# schematic_smd.net
KiCad netlist of a schematic drawn in EAGLE
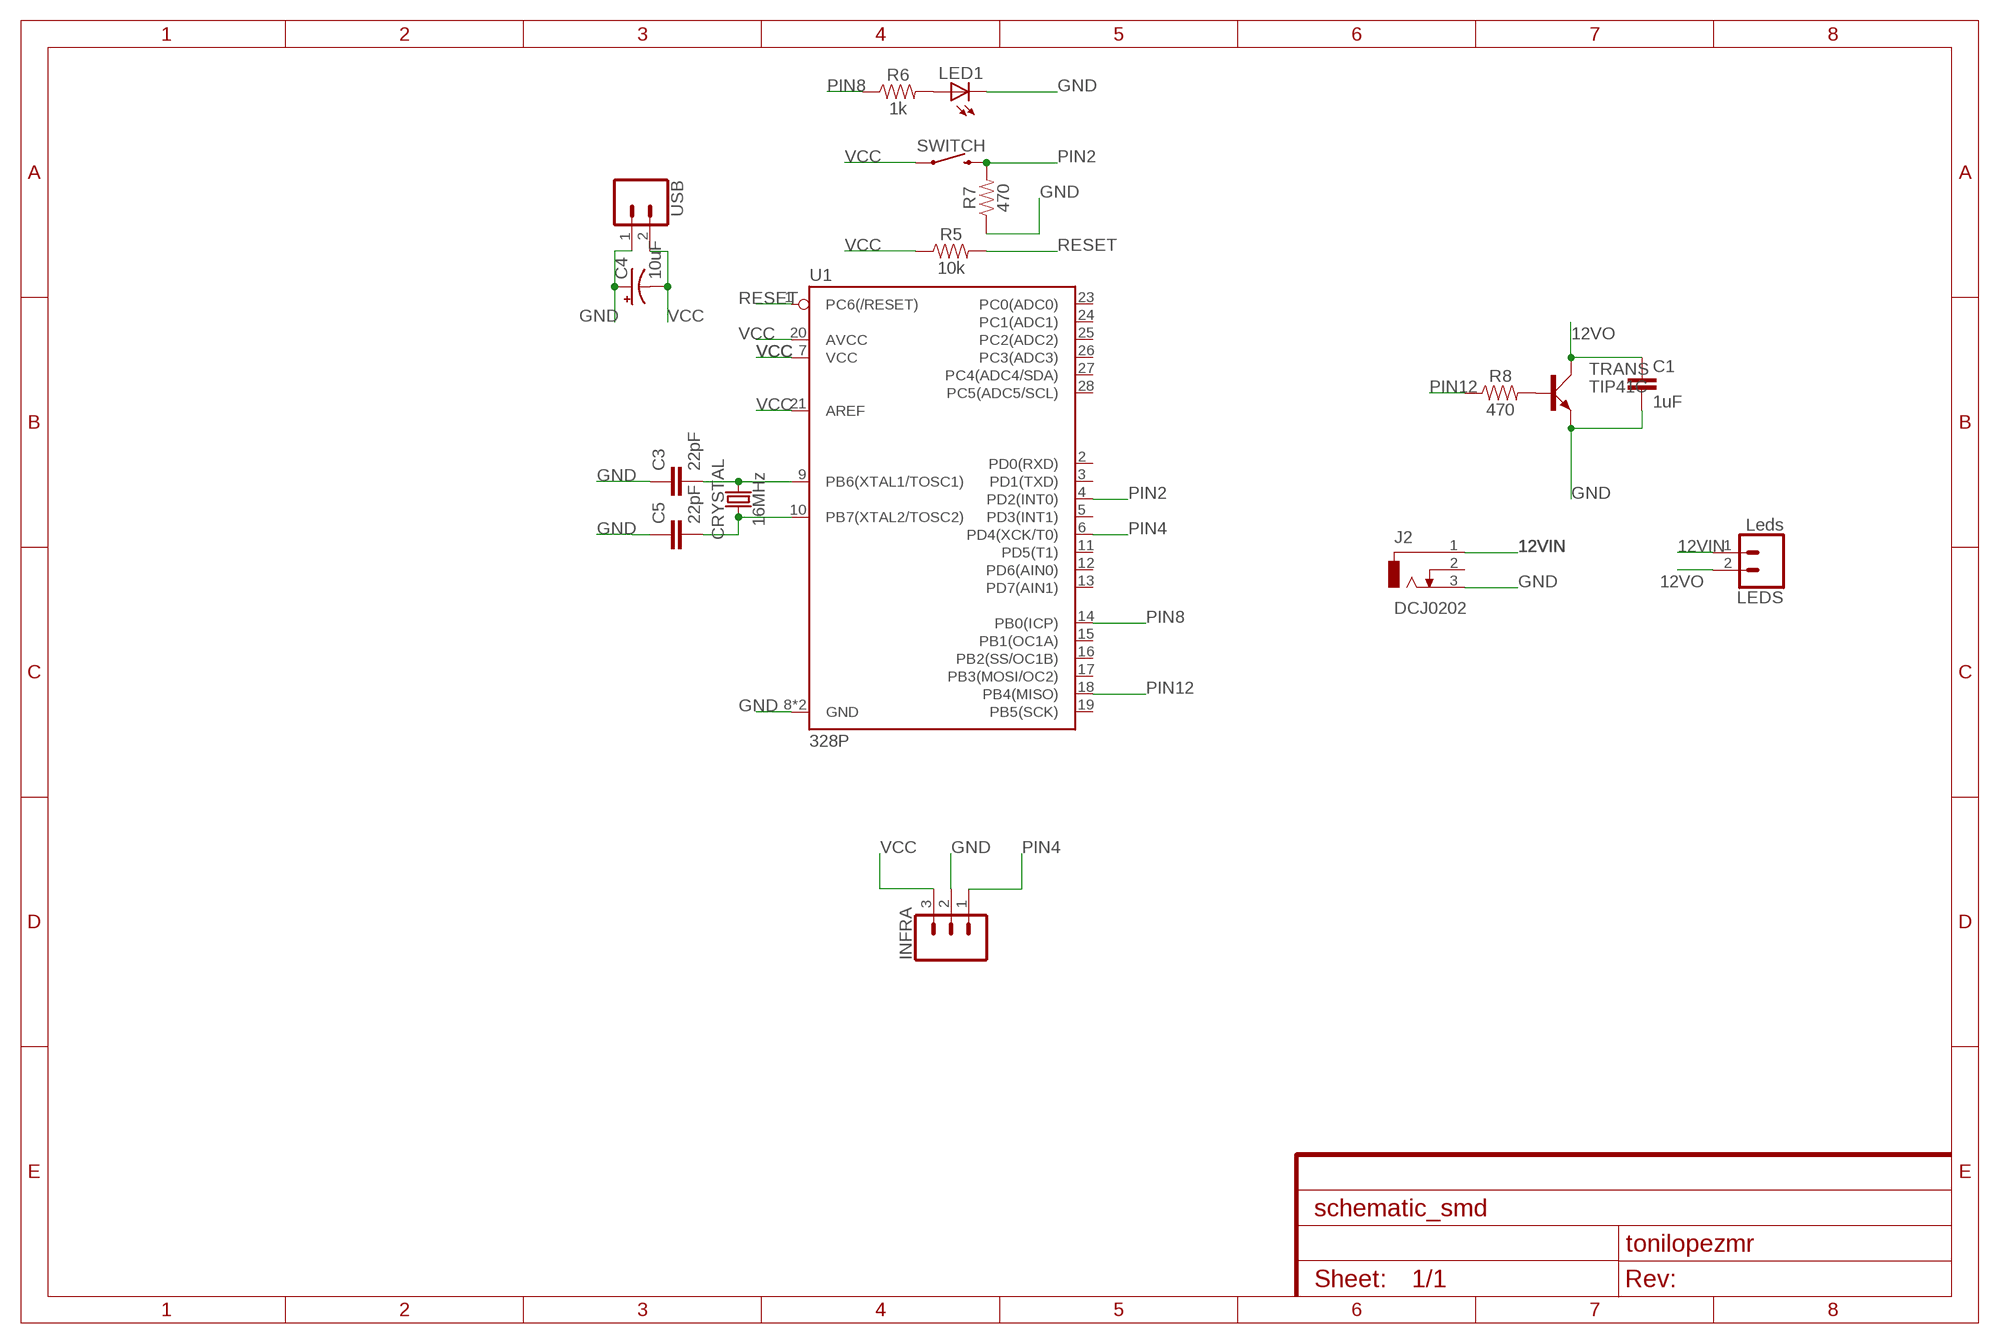
[diagram p0: schematic, sheet 1]

(export (version "E")
  (design (tool "Eeschema 10.0.6"))
  (components
    (comp (ref "C1")
      (value "1uF")
      (footprint "eagle-import:1206")
      (libsource (lib "eagle-import") (part "1.0UF-1206-50V-10%"))
    )
    (comp (ref "C3")
      (value "22pF")
      (footprint "eagle-import:1206")
      (libsource (lib "eagle-import") (part "1.0UF-1206-50V-10%"))
    )
    (comp (ref "C4")
      (value "10uF")
      (footprint "eagle-import:CPOL-RADIAL-2.5MM-5MM")
      (libsource (lib "eagle-import") (part "10UF-POLAR-RADIAL-2.5MM-25V-20%"))
    )
    (comp (ref "C5")
      (value "22pF")
      (footprint "eagle-import:1206")
      (libsource (lib "eagle-import") (part "1.0UF-1206-50V-10%"))
    )
    (comp (ref "CRYSTAL")
      (value "16MHz")
      (footprint "eagle-import:HC49US")
      (libsource (lib "eagle-import") (part "CRYSTAL-16MHZPTH-HC49US"))
    )
    (comp (ref "INFRA")
      (value "455-1750-1-ND")
      (footprint "eagle-import:1X03")
      (libsource (lib "eagle-import") (part "CONN_03"))
    )
    (comp (ref "J2")
      (value "DCJ0202")
      (footprint "eagle-import:DCJ0202")
      (libsource (lib "eagle-import") (part "DCJ0202"))
    )
    (comp (ref "LED1")
      (value "LED5MM")
      (footprint "eagle-import:LED5MM")
      (libsource (lib "eagle-import") (part "LED5MM"))
    )
    (comp (ref "LEDS")
      (value "Leds")
      (footprint "eagle-import:JST-2-PTH-KIT")
      (libsource (lib "eagle-import") (part "CONN_02JST-PTH-2-KIT"))
    )
    (comp (ref "R5")
      (value "10k")
      (footprint "eagle-import:0805")
      (libsource (lib "eagle-import") (part "0.22OHM-0805-1/4W-1%"))
    )
    (comp (ref "R6")
      (value "1k")
      (footprint "eagle-import:1206")
      (libsource (lib "eagle-import") (part "10OHM-1206-1/4W-1%"))
    )
    (comp (ref "R7")
      (value "470")
      (footprint "eagle-import:1206")
      (libsource (lib "eagle-import") (part "10OHM-1206-1/4W-1%"))
    )
    (comp (ref "R8")
      (value "470")
      (footprint "eagle-import:1206")
      (libsource (lib "eagle-import") (part "10OHM-1206-1/4W-1%"))
    )
    (comp (ref "SWITCH")
      (value "MOMENTARY-SWITCH-SPST-PTH-6.0MM")
      (footprint "eagle-import:TACTILE_SWITCH_PTH_6.0MM")
      (libsource (lib "eagle-import") (part "MOMENTARY-SWITCH-SPST-PTH-6.0MM"))
    )
    (comp (ref "TRANS")
      (value "TIP41C")
      (footprint "eagle-import:TO220AV")
      (libsource (lib "eagle-import") (part "TIP41C"))
    )
    (comp (ref "U1")
      (value "328P")
      (footprint "eagle-import:DIP28")
      (libsource (lib "eagle-import") (part "ATMEGA328P_PDIP"))
    )
    (comp (ref "USB")
      (value "CONN_02JST-PTH-2-KIT")
      (footprint "eagle-import:JST-2-PTH-KIT")
      (libsource (lib "eagle-import") (part "CONN_02JST-PTH-2-KIT"))
    )
  )
  (nets
    (net (code "1") (name "/12VIN") (class "Default")
      (node (ref "J2") (pin "1") (pinfunction "1_1") (pintype "passive"))
      (node (ref "LEDS") (pin "1") (pinfunction "1_1") (pintype "passive"))
    )
    (net (code "2") (name "/12VO") (class "Default")
      (node (ref "C1") (pin "1") (pinfunction "1_1") (pintype "passive"))
      (node (ref "LEDS") (pin "2") (pinfunction "2_2") (pintype "passive"))
      (node (ref "TRANS") (pin "C") (pinfunction "C_C") (pintype "passive"))
    )
    (net (code "3") (name "/GND") (class "Default")
      (node (ref "C1") (pin "2") (pinfunction "2_2") (pintype "passive"))
      (node (ref "C3") (pin "1") (pinfunction "1_1") (pintype "passive"))
      (node (ref "C4") (pin "1") (pinfunction "+_1") (pintype "passive"))
      (node (ref "C5") (pin "1") (pinfunction "1_1") (pintype "passive"))
      (node (ref "INFRA") (pin "2") (pinfunction "2_2") (pintype "passive"))
      (node (ref "J2") (pin "3") (pinfunction "3_3") (pintype "passive"))
      (node (ref "LED1") (pin "K") (pinfunction "C_K") (pintype "passive"))
      (node (ref "R7") (pin "1") (pinfunction "1_1") (pintype "passive"))
      (node (ref "TRANS") (pin "E") (pinfunction "E_E") (pintype "passive"))
      (node (ref "U1") (pin "22") (pinfunction "GND_22") (pintype "bidirectional"))
      (node (ref "U1") (pin "8") (pinfunction "GND_8") (pintype "bidirectional"))
      (node (ref "USB") (pin "1") (pinfunction "1_1") (pintype "passive"))
    )
    (net (code "4") (name "/PIN2") (class "Default")
      (node (ref "R7") (pin "2") (pinfunction "2_2") (pintype "passive"))
      (node (ref "SWITCH") (pin "3") (pinfunction "2_3") (pintype "passive"))
      (node (ref "U1") (pin "4") (pinfunction "PD2(INT0)_4") (pintype "bidirectional"))
    )
    (net (code "5") (name "/PIN4") (class "Default")
      (node (ref "INFRA") (pin "1") (pinfunction "1_1") (pintype "passive"))
      (node (ref "U1") (pin "6") (pinfunction "PD4(XCK/T0)_6") (pintype "bidirectional"))
    )
    (net (code "6") (name "/PIN8") (class "Default")
      (node (ref "R6") (pin "1") (pinfunction "1_1") (pintype "passive"))
      (node (ref "U1") (pin "14") (pinfunction "PB0(ICP)_14") (pintype "bidirectional"))
    )
    (net (code "7") (name "/PIN12") (class "Default")
      (node (ref "R8") (pin "1") (pinfunction "1_1") (pintype "passive"))
      (node (ref "U1") (pin "18") (pinfunction "PB4(MISO)_18") (pintype "bidirectional"))
    )
    (net (code "8") (name "/RESET") (class "Default")
      (node (ref "R5") (pin "2") (pinfunction "2_2") (pintype "passive"))
      (node (ref "U1") (pin "1") (pinfunction "PC6(/RESET)_1") (pintype "bidirectional"))
    )
    (net (code "9") (name "/VCC") (class "Default")
      (node (ref "C4") (pin "2") (pinfunction "-_2") (pintype "passive"))
      (node (ref "INFRA") (pin "3") (pinfunction "3_3") (pintype "passive"))
      (node (ref "R5") (pin "1") (pinfunction "1_1") (pintype "passive"))
      (node (ref "SWITCH") (pin "1") (pinfunction "1_1") (pintype "passive"))
      (node (ref "U1") (pin "20") (pinfunction "AVCC_20") (pintype "bidirectional"))
      (node (ref "U1") (pin "21") (pinfunction "AREF_21") (pintype "bidirectional"))
      (node (ref "U1") (pin "7") (pinfunction "VCC_7") (pintype "bidirectional"))
      (node (ref "USB") (pin "2") (pinfunction "2_2") (pintype "passive"))
    )
    (net (code "10") (name "Net-(LED1-PadA)") (class "Default")
      (node (ref "LED1") (pin "A") (pinfunction "A_A") (pintype "passive"))
      (node (ref "R6") (pin "2") (pinfunction "2_2") (pintype "passive"))
    )
    (net (code "11") (name "Net-(R8-Pad2)") (class "Default")
      (node (ref "R8") (pin "2") (pinfunction "2_2") (pintype "passive"))
      (node (ref "TRANS") (pin "B") (pinfunction "B_B") (pintype "passive"))
    )
    (net (code "12") (name "Net-(U1-PB6(XTAL1{slash}TOSC1))") (class "Default")
      (node (ref "C3") (pin "2") (pinfunction "2_2") (pintype "passive"))
      (node (ref "CRYSTAL") (pin "2") (pinfunction "2_2") (pintype "passive"))
      (node (ref "U1") (pin "9") (pinfunction "PB6(XTAL1/TOSC1)_9") (pintype "bidirectional"))
    )
    (net (code "13") (name "Net-(U1-PB7(XTAL2{slash}TOSC2))") (class "Default")
      (node (ref "C5") (pin "2") (pinfunction "2_2") (pintype "passive"))
      (node (ref "CRYSTAL") (pin "1") (pinfunction "1_1") (pintype "passive"))
      (node (ref "U1") (pin "10") (pinfunction "PB7(XTAL2/TOSC2)_10") (pintype "bidirectional"))
    )
    (net (code "14") (name "unconnected-(J2-Pad2)") (class "Default")
      (node (ref "J2") (pin "2") (pinfunction "2_2") (pintype "passive"))
    )
    (net (code "15") (name "unconnected-(U1-PB1(OC1A)-Pad15)") (class "Default")
      (node (ref "U1") (pin "15") (pinfunction "PB1(OC1A)_15") (pintype "bidirectional"))
    )
    (net (code "16") (name "unconnected-(U1-PB2(SS{slash}OC1B)-Pad16)") (class "Default")
      (node (ref "U1") (pin "16") (pinfunction "PB2(SS/OC1B)_16") (pintype "bidirectional"))
    )
    (net (code "17") (name "unconnected-(U1-PB3(MOSI{slash}OC2)-Pad17)") (class "Default")
      (node (ref "U1") (pin "17") (pinfunction "PB3(MOSI/OC2)_17") (pintype "bidirectional"))
    )
    (net (code "18") (name "unconnected-(U1-PB5(SCK)-Pad19)") (class "Default")
      (node (ref "U1") (pin "19") (pinfunction "PB5(SCK)_19") (pintype "bidirectional"))
    )
    (net (code "19") (name "unconnected-(U1-PC0(ADC0)-Pad23)") (class "Default")
      (node (ref "U1") (pin "23") (pinfunction "PC0(ADC0)_23") (pintype "bidirectional"))
    )
    (net (code "20") (name "unconnected-(U1-PC1(ADC1)-Pad24)") (class "Default")
      (node (ref "U1") (pin "24") (pinfunction "PC1(ADC1)_24") (pintype "bidirectional"))
    )
    (net (code "21") (name "unconnected-(U1-PC2(ADC2)-Pad25)") (class "Default")
      (node (ref "U1") (pin "25") (pinfunction "PC2(ADC2)_25") (pintype "bidirectional"))
    )
    (net (code "22") (name "unconnected-(U1-PC3(ADC3)-Pad26)") (class "Default")
      (node (ref "U1") (pin "26") (pinfunction "PC3(ADC3)_26") (pintype "bidirectional"))
    )
    (net (code "23") (name "unconnected-(U1-PC4(ADC4{slash}SDA)-Pad27)") (class "Default")
      (node (ref "U1") (pin "27") (pinfunction "PC4(ADC4/SDA)_27") (pintype "bidirectional"))
    )
    (net (code "24") (name "unconnected-(U1-PC5(ADC5{slash}SCL)-Pad28)") (class "Default")
      (node (ref "U1") (pin "28") (pinfunction "PC5(ADC5/SCL)_28") (pintype "bidirectional"))
    )
    (net (code "25") (name "unconnected-(U1-PD0(RXD)-Pad2)") (class "Default")
      (node (ref "U1") (pin "2") (pinfunction "PD0(RXD)_2") (pintype "bidirectional"))
    )
    (net (code "26") (name "unconnected-(U1-PD1(TXD)-Pad3)") (class "Default")
      (node (ref "U1") (pin "3") (pinfunction "PD1(TXD)_3") (pintype "bidirectional"))
    )
    (net (code "27") (name "unconnected-(U1-PD3(INT1)-Pad5)") (class "Default")
      (node (ref "U1") (pin "5") (pinfunction "PD3(INT1)_5") (pintype "bidirectional"))
    )
    (net (code "28") (name "unconnected-(U1-PD5(T1)-Pad11)") (class "Default")
      (node (ref "U1") (pin "11") (pinfunction "PD5(T1)_11") (pintype "bidirectional"))
    )
    (net (code "29") (name "unconnected-(U1-PD6(AIN0)-Pad12)") (class "Default")
      (node (ref "U1") (pin "12") (pinfunction "PD6(AIN0)_12") (pintype "bidirectional"))
    )
    (net (code "30") (name "unconnected-(U1-PD7(AIN1)-Pad13)") (class "Default")
      (node (ref "U1") (pin "13") (pinfunction "PD7(AIN1)_13") (pintype "bidirectional"))
    )
  )
)
